# board2.net
KiCad netlist of a schematic drawn in EAGLE
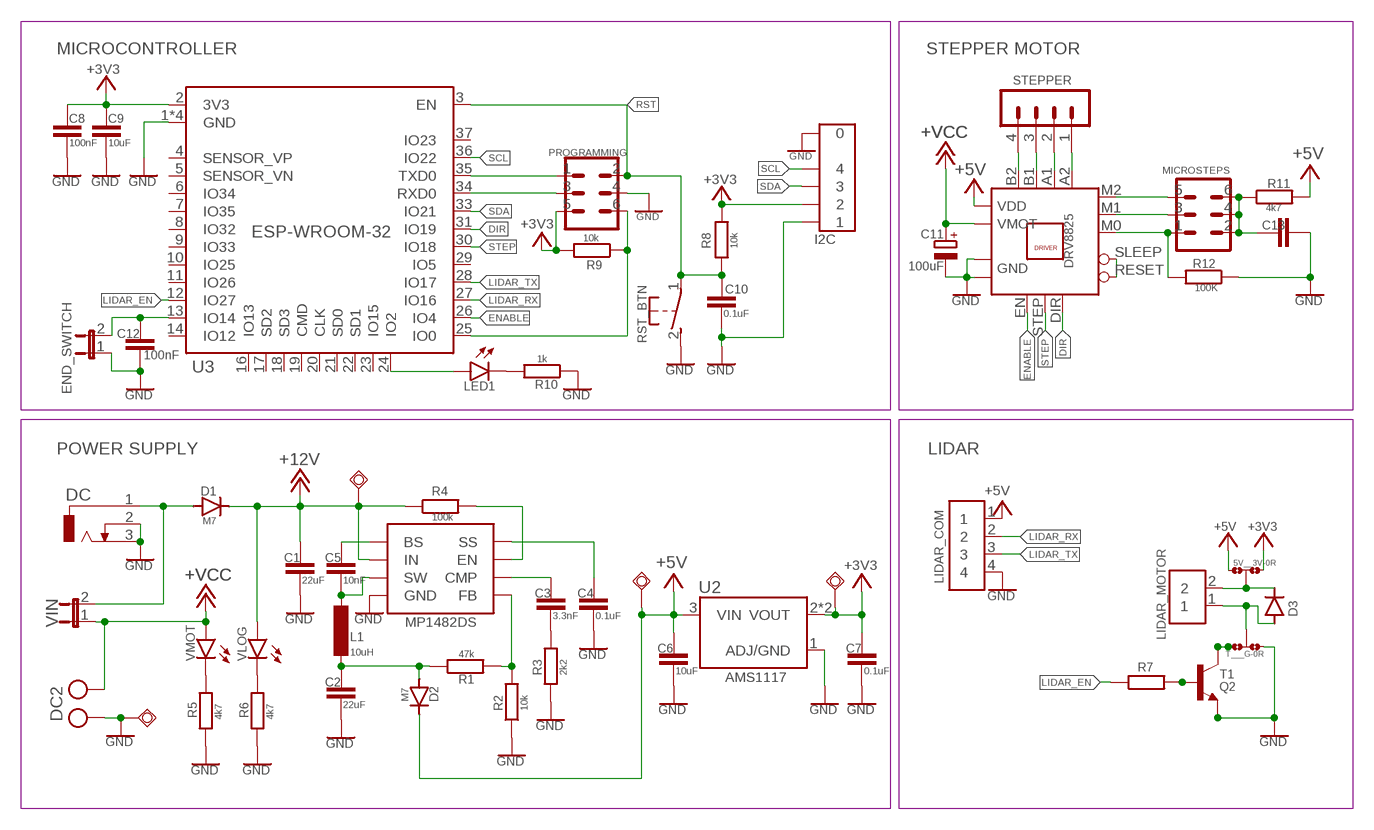
[diagram p0: schematic, sheet 1]

(export (version "E")
  (design (tool "Eeschema 10.0.6"))
  (components
    (comp (ref "3V3")
      (value "TPSQTP07R")
      (footprint "eagle-import:TP07R")
      (libsource (lib "eagle-import") (part "TPSQTP07R"))
    )
    (comp (ref "5V")
      (value "TPSQTP07R")
      (footprint "eagle-import:TP07R")
      (libsource (lib "eagle-import") (part "TPSQTP07R"))
    )
    (comp (ref "5V__3V")
      (value "0R-JUMPA")
      (footprint "eagle-import:A0R-JMP")
      (libsource (lib "eagle-import") (part "0R-JUMPA"))
    )
    (comp (ref "12V")
      (value "TPSQTP07R")
      (footprint "eagle-import:TP07R")
      (libsource (lib "eagle-import") (part "TPSQTP07R"))
    )
    (comp (ref "C1")
      (value "22uF")
      (footprint "eagle-import:C1210K")
      (libsource (lib "eagle-import") (part "C-EUC1210K"))
    )
    (comp (ref "C2")
      (value "22uF")
      (footprint "eagle-import:C1210K")
      (libsource (lib "eagle-import") (part "C-EUC1210K"))
    )
    (comp (ref "C3")
      (value "3.3nF")
      (footprint "eagle-import:C0805K")
      (libsource (lib "eagle-import") (part "C-EUC0805K"))
    )
    (comp (ref "C4")
      (value "0.1uF")
      (footprint "eagle-import:C0805K")
      (libsource (lib "eagle-import") (part "C-EUC0805K"))
    )
    (comp (ref "C5")
      (value "10nF")
      (footprint "eagle-import:C0805K")
      (libsource (lib "eagle-import") (part "C-EUC0805K"))
    )
    (comp (ref "C6")
      (value "10uF")
      (footprint "eagle-import:C1210K")
      (libsource (lib "eagle-import") (part "C-EUC1210K"))
    )
    (comp (ref "C7")
      (value "0.1uF")
      (footprint "eagle-import:C1210K")
      (libsource (lib "eagle-import") (part "C-EUC1210K"))
    )
    (comp (ref "C8")
      (value "100nF")
      (footprint "eagle-import:C0805K")
      (libsource (lib "eagle-import") (part "C-EUC0805K"))
    )
    (comp (ref "C9")
      (value "10uF")
      (footprint "eagle-import:C1210K")
      (libsource (lib "eagle-import") (part "C-EUC1210K"))
    )
    (comp (ref "C10")
      (value "0.1uF")
      (footprint "eagle-import:C0805K")
      (libsource (lib "eagle-import") (part "C-EUC0805K"))
    )
    (comp (ref "C11")
      (value "100uF")
      (footprint "eagle-import:E3,5-8")
      (libsource (lib "eagle-import") (part "CPOL-EUE3.5-8"))
    )
    (comp (ref "C12")
      (value "100nF")
      (footprint "eagle-import:C0805K")
      (libsource (lib "eagle-import") (part "C-EUC0805K"))
    )
    (comp (ref "C13")
      (value "C-EUC0805K")
      (footprint "eagle-import:C0805K")
      (libsource (lib "eagle-import") (part "C-EUC0805K"))
    )
    (comp (ref "D1")
      (value "M7")
      (footprint "eagle-import:DO-214AC")
      (libsource (lib "eagle-import") (part "DIODE-DO-214AC"))
    )
    (comp (ref "D2")
      (value "M7")
      (footprint "eagle-import:DO-214AC")
      (libsource (lib "eagle-import") (part "DIODE-DO-214AC"))
    )
    (comp (ref "D3")
      (value "M7")
      (footprint "eagle-import:DO-214AC")
      (libsource (lib "eagle-import") (part "DIODE-DO-214AC"))
    )
    (comp (ref "DC")
      (value "DCJ0202")
      (footprint "eagle-import:DCJ0202")
      (libsource (lib "eagle-import") (part "DCJ0202"))
    )
    (comp (ref "DC2")
      (value "DC2")
      (footprint "eagle-import:AK500_2-H")
      (libsource (lib "eagle-import") (part "AK500/2-H"))
    )
    (comp (ref "DRIVER")
      (value "DRV8825_PCB")
      (footprint "eagle-import:DRV8825_PCB")
      (libsource (lib "eagle-import") (part "DRV8825_PCB"))
    )
    (comp (ref "DRV8825")
      (value "DRV8825_H")
      (footprint "eagle-import:DRV8825_H")
      (libsource (lib "eagle-import") (part "DRV8825_H"))
    )
    (comp (ref "END_SWITCH")
      (value "END_SWITCH")
      (footprint "eagle-import:JP1")
      (libsource (lib "eagle-import") (part "JP1E"))
    )
    (comp (ref "GND")
      (value "TPSQTP07R")
      (footprint "eagle-import:TP07R")
      (libsource (lib "eagle-import") (part "TPSQTP07R"))
    )
    (comp (ref "I2C")
      (value "SM04B-SRSS-TB(LF)(SN)")
      (footprint "eagle-import:JST_SM04B-SRSS-TB(LF)(SN)")
      (fields (field (name "MF") "JST Sales"))
      (libsource (lib "eagle-import") (part "SM04B-SRSS-TB(LF)(SN)"))
    )
    (comp (ref "L1")
      (value "10uH")
      (footprint "eagle-import:L5650M")
      (libsource (lib "eagle-import") (part "L-EUL5650M"))
    )
    (comp (ref "LED1")
      (value "0")
      (footprint "eagle-import:CHIP-LED0805")
      (libsource (lib "eagle-import") (part "LEDCHIP-LED0805"))
    )
    (comp (ref "LIDAR_COM")
      (value "4PIN")
      (footprint "eagle-import:B4B-PH-K-S")
      (libsource (lib "eagle-import") (part "4PIN"))
    )
    (comp (ref "LIDAR_MOTOR")
      (value "2PIN")
      (footprint "eagle-import:B2B-PH-K-S")
      (libsource (lib "eagle-import") (part "2PIN"))
    )
    (comp (ref "MICROSTEPS")
      (value "MicroSteps")
      (footprint "eagle-import:MA03-2")
      (libsource (lib "eagle-import") (part "MA03-2"))
    )
    (comp (ref "PROGRAMMING")
      (value "Programming")
      (footprint "eagle-import:MA03-2")
      (libsource (lib "eagle-import") (part "MA03-2"))
    )
    (comp (ref "Q2")
      (value "BC846ALT1SMD")
      (footprint "eagle-import:SOT23")
      (libsource (lib "eagle-import") (part "BC846SMDALT1"))
    )
    (comp (ref "R1")
      (value "47k")
      (footprint "eagle-import:R0805W")
      (libsource (lib "eagle-import") (part "R-EU_R0805W"))
    )
    (comp (ref "R2")
      (value "10k")
      (footprint "eagle-import:R0805W")
      (libsource (lib "eagle-import") (part "R-EU_R0805W"))
    )
    (comp (ref "R3")
      (value "2k2")
      (footprint "eagle-import:R0805W")
      (libsource (lib "eagle-import") (part "R-EU_R0805W"))
    )
    (comp (ref "R4")
      (value "100k")
      (footprint "eagle-import:R0805W")
      (libsource (lib "eagle-import") (part "R-EU_R0805W"))
    )
    (comp (ref "R5")
      (value "4k7")
      (footprint "eagle-import:R0805W")
      (libsource (lib "eagle-import") (part "R-EU_R0805W"))
    )
    (comp (ref "R6")
      (value "4k7")
      (footprint "eagle-import:R0805W")
      (libsource (lib "eagle-import") (part "R-EU_R0805W"))
    )
    (comp (ref "R7")
      (value "R")
      (footprint "eagle-import:R0805W")
      (libsource (lib "eagle-import") (part "R-EU_R0805W"))
    )
    (comp (ref "R8")
      (value "10k")
      (footprint "eagle-import:R0805W")
      (libsource (lib "eagle-import") (part "R-EU_R0805W"))
    )
    (comp (ref "R9")
      (value "10k")
      (footprint "eagle-import:R0805W")
      (libsource (lib "eagle-import") (part "R-EU_R0805W"))
    )
    (comp (ref "R10")
      (value "1k")
      (footprint "eagle-import:R0805W")
      (libsource (lib "eagle-import") (part "R-EU_R0805W"))
    )
    (comp (ref "R11")
      (value "4k7")
      (footprint "eagle-import:R0805W")
      (libsource (lib "eagle-import") (part "R-EU_R0805W"))
    )
    (comp (ref "R12")
      (value "100K")
      (footprint "eagle-import:R0805W")
      (libsource (lib "eagle-import") (part "R-EU_R0805W"))
    )
    (comp (ref "RST_BTN")
      (value "DTSM-3")
      (footprint "eagle-import:DTSM-3")
      (libsource (lib "eagle-import") (part "DTSM-3"))
    )
    (comp (ref "STEPPER")
      (value "Stepper")
      (footprint "eagle-import:MA04-1")
      (libsource (lib "eagle-import") (part "MA04-1"))
    )
    (comp (ref "T1")
      (value "BD139_BCXXX")
      (footprint "eagle-import:TO126+TO92")
      (libsource (lib "eagle-import") (part "BDBC"))
    )
    (comp (ref "T___G")
      (value "0R-JUMPB")
      (footprint "eagle-import:B0R-JMP")
      (libsource (lib "eagle-import") (part "0R-JUMPB"))
    )
    (comp (ref "U1")
      (value "MP1482DS")
      (footprint "eagle-import:SOIC127P600X175-8N")
      (fields (field (name "MP1482DS") "MP1482DS"))
      (libsource (lib "eagle-import") (part "MP1482DS"))
    )
    (comp (ref "U2")
      (value "AMS1117")
      (footprint "eagle-import:SOT229P700X180-4N")
      (fields (field (name "MF") "Advanced Monolithic Systems"))
      (libsource (lib "eagle-import") (part "AMS1117"))
    )
    (comp (ref "U3")
      (value "ESP-WROOM-32")
      (footprint "eagle-import:ESP-WROOM-32")
      (libsource (lib "eagle-import") (part "ESP-WROOM-32"))
    )
    (comp (ref "VIN")
      (value "JUMPER")
      (footprint "eagle-import:JP1")
      (libsource (lib "eagle-import") (part "JP1E"))
    )
    (comp (ref "VLOG")
      (value "00")
      (footprint "eagle-import:CHIP-LED0805")
      (libsource (lib "eagle-import") (part "LEDCHIP-LED0805"))
    )
    (comp (ref "VMOT")
      (value "00")
      (footprint "eagle-import:CHIP-LED0805")
      (libsource (lib "eagle-import") (part "LEDCHIP-LED0805"))
    )
  )
  (nets
    (net (code "1") (name "+3V3") (class "Default")
      (node (ref "3V3") (pin "TP") (pinfunction "TP_TP") (pintype "input"))
      (node (ref "5V__3V") (pin "1") (pinfunction "1_1") (pintype "passive"))
      (node (ref "5V__3V") (pin "2") (pinfunction "2_2") (pintype "passive"))
      (node (ref "C7") (pin "1") (pinfunction "1_1") (pintype "passive"))
      (node (ref "C8") (pin "1") (pinfunction "1_1") (pintype "passive"))
      (node (ref "C9") (pin "1") (pinfunction "1_1") (pintype "passive"))
      (node (ref "D3") (pin "C") (pinfunction "C_C") (pintype "passive"))
      (node (ref "I2C") (pin "2") (pinfunction "2_2") (pintype "passive"))
      (node (ref "LIDAR_MOTOR") (pin "2") (pinfunction "2_2") (pintype "bidirectional"))
      (node (ref "PROGRAMMING") (pin "5") (pinfunction "5_5") (pintype "passive"))
      (node (ref "R8") (pin "1") (pinfunction "1_1") (pintype "passive"))
      (node (ref "R9") (pin "2") (pinfunction "2_2") (pintype "passive"))
      (node (ref "U2") (pin "2") (pinfunction "VOUT_2") (pintype "output"))
      (node (ref "U2") (pin "4") (pinfunction "VOUT_4") (pintype "output"))
      (node (ref "U3") (pin "2") (pinfunction "3V3_2") (pintype "power_in"))
    )
    (net (code "2") (name "+5V") (class "Default")
      (node (ref "5V") (pin "TP") (pinfunction "TP_TP") (pintype "input"))
      (node (ref "5V__3V") (pin "3") (pinfunction "3_3") (pintype "passive"))
      (node (ref "C6") (pin "2") (pinfunction "2_2") (pintype "passive"))
      (node (ref "D2") (pin "C") (pinfunction "C_C") (pintype "passive"))
      (node (ref "DRV8825") (pin "FAULT") (pinfunction "VDD_FAULT") (pintype "power_in"))
      (node (ref "LIDAR_COM") (pin "1") (pinfunction "1_1") (pintype "bidirectional"))
      (node (ref "R11") (pin "2") (pinfunction "2_2") (pintype "passive"))
      (node (ref "U2") (pin "3") (pinfunction "VIN_3") (pintype "input"))
    )
    (net (code "3") (name "+12V") (class "Default")
      (node (ref "12V") (pin "TP") (pinfunction "TP_TP") (pintype "input"))
      (node (ref "C1") (pin "2") (pinfunction "2_2") (pintype "passive"))
      (node (ref "D1") (pin "C") (pinfunction "C_C") (pintype "passive"))
      (node (ref "R4") (pin "1") (pinfunction "1_1") (pintype "passive"))
      (node (ref "U1") (pin "2") (pinfunction "IN_2") (pintype "power_in"))
      (node (ref "VLOG") (pin "A") (pinfunction "A_A") (pintype "passive"))
    )
    (net (code "4") (name "+VCC") (class "Default")
      (node (ref "C11") (pin "+") (pinfunction "+_+") (pintype "passive"))
      (node (ref "DC2") (pin "2") (pinfunction "KL_2") (pintype "passive"))
      (node (ref "DRV8825") (pin "VMOT") (pinfunction "VMOT_VMOT") (pintype "power_in"))
      (node (ref "DRV8825") (pin "VMOT1") (pinfunction "VMOT_VMOT1") (pintype "power_in"))
      (node (ref "VIN") (pin "1") (pinfunction "1_1") (pintype "passive"))
      (node (ref "VMOT") (pin "A") (pinfunction "A_A") (pintype "passive"))
    )
    (net (code "5") (name "DIR") (class "Default")
      (node (ref "DRV8825") (pin "DIR") (pinfunction "DIR_DIR") (pintype "input"))
      (node (ref "U3") (pin "31") (pinfunction "IO19_31") (pintype "bidirectional"))
    )
    (net (code "6") (name "ENABLE") (class "Default")
      (node (ref "DRV8825") (pin "EN") (pinfunction "EN_EN") (pintype "input"))
      (node (ref "U3") (pin "26") (pinfunction "IO4_26") (pintype "bidirectional"))
    )
    (net (code "7") (name "GND") (class "Default")
      (node (ref "C1") (pin "1") (pinfunction "1_1") (pintype "passive"))
      (node (ref "C10") (pin "2") (pinfunction "2_2") (pintype "passive"))
      (node (ref "C11") (pin "-") (pinfunction "-_-") (pintype "passive"))
      (node (ref "C12") (pin "1") (pinfunction "1_1") (pintype "passive"))
      (node (ref "C13") (pin "2") (pinfunction "2_2") (pintype "passive"))
      (node (ref "C2") (pin "2") (pinfunction "2_2") (pintype "passive"))
      (node (ref "C4") (pin "1") (pinfunction "1_1") (pintype "passive"))
      (node (ref "C6") (pin "1") (pinfunction "1_1") (pintype "passive"))
      (node (ref "C7") (pin "2") (pinfunction "2_2") (pintype "passive"))
      (node (ref "C8") (pin "2") (pinfunction "2_2") (pintype "passive"))
      (node (ref "C9") (pin "2") (pinfunction "2_2") (pintype "passive"))
      (node (ref "DC") (pin "2") (pinfunction "2_2") (pintype "passive"))
      (node (ref "DC") (pin "3") (pinfunction "3_3") (pintype "passive"))
      (node (ref "DC2") (pin "1") (pinfunction "KL_1") (pintype "passive"))
      (node (ref "DRV8825") (pin "GND") (pinfunction "GND_GND") (pintype "power_in"))
      (node (ref "DRV8825") (pin "GND1") (pinfunction "GMOT_GND1") (pintype "power_in"))
      (node (ref "END_SWITCH") (pin "1") (pinfunction "1_1") (pintype "passive"))
      (node (ref "GND") (pin "TP") (pinfunction "TP_TP") (pintype "input"))
      (node (ref "I2C") (pin "1") (pinfunction "1_1") (pintype "passive"))
      (node (ref "I2C") (pin "S1") (pinfunction "0_S1") (pintype "passive"))
      (node (ref "I2C") (pin "S2") (pinfunction "0_S2") (pintype "passive"))
      (node (ref "LIDAR_COM") (pin "4") (pinfunction "4_4") (pintype "bidirectional"))
      (node (ref "PROGRAMMING") (pin "4") (pinfunction "4_4") (pintype "passive"))
      (node (ref "Q2") (pin "2") (pinfunction "E_2") (pintype "passive"))
      (node (ref "R10") (pin "1") (pinfunction "1_1") (pintype "passive"))
      (node (ref "R12") (pin "1") (pinfunction "1_1") (pintype "passive"))
      (node (ref "R2") (pin "1") (pinfunction "1_1") (pintype "passive"))
      (node (ref "R3") (pin "1") (pinfunction "1_1") (pintype "passive"))
      (node (ref "R5") (pin "1") (pinfunction "1_1") (pintype "passive"))
      (node (ref "R6") (pin "1") (pinfunction "1_1") (pintype "passive"))
      (node (ref "RST_BTN") (pin "2") (pinfunction "2_2") (pintype "passive"))
      (node (ref "T1") (pin "E") (pinfunction "E_E") (pintype "passive"))
      (node (ref "T1") (pin "E1") (pinfunction "E_E1") (pintype "passive"))
      (node (ref "T___G") (pin "3") (pinfunction "3_3") (pintype "passive"))
      (node (ref "U1") (pin "4") (pinfunction "GND_4") (pintype "power_in"))
      (node (ref "U2") (pin "1") (pinfunction "ADJ/GND_1") (pintype "power_in"))
      (node (ref "U3") (pin "1") (pinfunction "GND_1") (pintype "power_in"))
      (node (ref "U3") (pin "15") (pinfunction "GND_15") (pintype "power_in"))
      (node (ref "U3") (pin "38") (pinfunction "GND_38") (pintype "power_in"))
      (node (ref "U3") (pin "GND") (pinfunction "GND_GND") (pintype "power_in"))
    )
    (net (code "8") (name "LIDAR_EN") (class "Default")
      (node (ref "R7") (pin "1") (pinfunction "1_1") (pintype "passive"))
      (node (ref "U3") (pin "12") (pinfunction "IO27_12") (pintype "bidirectional"))
    )
    (net (code "9") (name "LIDAR_RX") (class "Default")
      (node (ref "LIDAR_COM") (pin "2") (pinfunction "2_2") (pintype "bidirectional"))
      (node (ref "U3") (pin "27") (pinfunction "IO16_27") (pintype "bidirectional"))
    )
    (net (code "10") (name "LIDAR_TX") (class "Default")
      (node (ref "LIDAR_COM") (pin "3") (pinfunction "3_3") (pintype "bidirectional"))
      (node (ref "U3") (pin "28") (pinfunction "IO17_28") (pintype "bidirectional"))
    )
    (net (code "11") (name "Net-(C2-Pad1)") (class "Default")
      (node (ref "C2") (pin "1") (pinfunction "1_1") (pintype "passive"))
      (node (ref "D2") (pin "A") (pinfunction "A_A") (pintype "passive"))
      (node (ref "L1") (pin "1") (pinfunction "1_1") (pintype "passive"))
      (node (ref "R1") (pin "1") (pinfunction "1_1") (pintype "passive"))
    )
    (net (code "12") (name "Net-(C3-Pad1)") (class "Default")
      (node (ref "C3") (pin "1") (pinfunction "1_1") (pintype "passive"))
      (node (ref "R3") (pin "2") (pinfunction "2_2") (pintype "passive"))
    )
    (net (code "13") (name "Net-(C13-Pad1)") (class "Default")
      (node (ref "C13") (pin "1") (pinfunction "1_1") (pintype "passive"))
      (node (ref "MICROSTEPS") (pin "2") (pinfunction "2_2") (pintype "passive"))
      (node (ref "MICROSTEPS") (pin "4") (pinfunction "4_4") (pintype "passive"))
      (node (ref "MICROSTEPS") (pin "6") (pinfunction "6_6") (pintype "passive"))
      (node (ref "R11") (pin "1") (pinfunction "1_1") (pintype "passive"))
    )
    (net (code "14") (name "Net-(D1-PadA)") (class "Default")
      (node (ref "D1") (pin "A") (pinfunction "A_A") (pintype "passive"))
      (node (ref "DC") (pin "1") (pinfunction "1_1") (pintype "passive"))
      (node (ref "VIN") (pin "2") (pinfunction "2_2") (pintype "passive"))
    )
    (net (code "15") (name "Net-(D3-PadA)") (class "Default")
      (node (ref "D3") (pin "A") (pinfunction "A_A") (pintype "passive"))
      (node (ref "LIDAR_MOTOR") (pin "1") (pinfunction "1_1") (pintype "bidirectional"))
      (node (ref "T___G") (pin "2") (pinfunction "2_2") (pintype "passive"))
    )
    (net (code "16") (name "Net-(DRV8825-PadA1)") (class "Default")
      (node (ref "DRV8825") (pin "A1") (pinfunction "A1_A1") (pintype "bidirectional"))
      (node (ref "STEPPER") (pin "2") (pinfunction "2_2") (pintype "passive"))
    )
    (net (code "17") (name "Net-(DRV8825-PadA2)") (class "Default")
      (node (ref "DRV8825") (pin "A2") (pinfunction "A2_A2") (pintype "bidirectional"))
      (node (ref "STEPPER") (pin "1") (pinfunction "1_1") (pintype "passive"))
    )
    (net (code "18") (name "Net-(DRV8825-PadB1)") (class "Default")
      (node (ref "DRV8825") (pin "B1") (pinfunction "B1_B1") (pintype "bidirectional"))
      (node (ref "STEPPER") (pin "3") (pinfunction "3_3") (pintype "passive"))
    )
    (net (code "19") (name "Net-(DRV8825-PadB2)") (class "Default")
      (node (ref "DRV8825") (pin "B2") (pinfunction "B2_B2") (pintype "bidirectional"))
      (node (ref "STEPPER") (pin "4") (pinfunction "4_4") (pintype "passive"))
    )
    (net (code "20") (name "Net-(DRV8825-PadM0)") (class "Default")
      (node (ref "DRV8825") (pin "M0") (pinfunction "M0_M0") (pintype "input"))
      (node (ref "MICROSTEPS") (pin "1") (pinfunction "1_1") (pintype "passive"))
      (node (ref "R12") (pin "2") (pinfunction "2_2") (pintype "passive"))
    )
    (net (code "21") (name "Net-(DRV8825-PadM1)") (class "Default")
      (node (ref "DRV8825") (pin "M1") (pinfunction "M1_M1") (pintype "input"))
      (node (ref "MICROSTEPS") (pin "3") (pinfunction "3_3") (pintype "passive"))
    )
    (net (code "22") (name "Net-(DRV8825-PadM2)") (class "Default")
      (node (ref "DRV8825") (pin "M2") (pinfunction "M2_M2") (pintype "input"))
      (node (ref "MICROSTEPS") (pin "5") (pinfunction "5_5") (pintype "passive"))
    )
    (net (code "23") (name "Net-(DRV8825-PadRESET)") (class "Default")
      (node (ref "DRV8825") (pin "RESET") (pinfunction "RESET_RESET") (pintype "bidirectional"))
      (node (ref "DRV8825") (pin "SLEEP") (pinfunction "SLEEP_SLEEP") (pintype "bidirectional"))
    )
    (net (code "24") (name "Net-(LED1-PadC)") (class "Default")
      (node (ref "LED1") (pin "C") (pinfunction "C_C") (pintype "passive"))
      (node (ref "R10") (pin "2") (pinfunction "2_2") (pintype "passive"))
    )
    (net (code "25") (name "Net-(Q2-B)") (class "Default")
      (node (ref "Q2") (pin "1") (pinfunction "B_1") (pintype "passive"))
      (node (ref "R7") (pin "2") (pinfunction "2_2") (pintype "passive"))
      (node (ref "T1") (pin "B") (pinfunction "B_B") (pintype "passive"))
    )
    (net (code "26") (name "Net-(Q2-C)") (class "Default")
      (node (ref "Q2") (pin "3") (pinfunction "C_3") (pintype "passive"))
      (node (ref "T1") (pin "C") (pinfunction "C_C") (pintype "passive"))
      (node (ref "T___G") (pin "1") (pinfunction "1_1") (pintype "passive"))
    )
    (net (code "27") (name "Net-(R5-Pad2)") (class "Default")
      (node (ref "R5") (pin "2") (pinfunction "2_2") (pintype "passive"))
      (node (ref "VMOT") (pin "C") (pinfunction "C_C") (pintype "passive"))
    )
    (net (code "28") (name "Net-(R6-Pad2)") (class "Default")
      (node (ref "R6") (pin "2") (pinfunction "2_2") (pintype "passive"))
      (node (ref "VLOG") (pin "C") (pinfunction "C_C") (pintype "passive"))
    )
    (net (code "29") (name "Net-(U1-BS)") (class "Default")
      (node (ref "C5") (pin "2") (pinfunction "2_2") (pintype "passive"))
      (node (ref "U1") (pin "1") (pinfunction "BS_1") (pintype "bidirectional"))
    )
    (net (code "30") (name "Net-(U1-CMP)") (class "Default")
      (node (ref "C3") (pin "2") (pinfunction "2_2") (pintype "passive"))
      (node (ref "U1") (pin "6") (pinfunction "CMP_6") (pintype "bidirectional"))
    )
    (net (code "31") (name "Net-(U1-EN)") (class "Default")
      (node (ref "R4") (pin "2") (pinfunction "2_2") (pintype "passive"))
      (node (ref "U1") (pin "7") (pinfunction "EN_7") (pintype "bidirectional"))
    )
    (net (code "32") (name "Net-(U1-FB)") (class "Default")
      (node (ref "R1") (pin "2") (pinfunction "2_2") (pintype "passive"))
      (node (ref "R2") (pin "2") (pinfunction "2_2") (pintype "passive"))
      (node (ref "U1") (pin "5") (pinfunction "FB_5") (pintype "bidirectional"))
    )
    (net (code "33") (name "Net-(U1-SS)") (class "Default")
      (node (ref "C4") (pin "2") (pinfunction "2_2") (pintype "passive"))
      (node (ref "U1") (pin "8") (pinfunction "SS_8") (pintype "bidirectional"))
    )
    (net (code "34") (name "Net-(U1-SW)") (class "Default")
      (node (ref "C5") (pin "1") (pinfunction "1_1") (pintype "passive"))
      (node (ref "L1") (pin "2") (pinfunction "2_2") (pintype "passive"))
      (node (ref "U1") (pin "3") (pinfunction "SW_3") (pintype "bidirectional"))
    )
    (net (code "35") (name "Net-(U3-IO0)") (class "Default")
      (node (ref "PROGRAMMING") (pin "6") (pinfunction "6_6") (pintype "passive"))
      (node (ref "R9") (pin "1") (pinfunction "1_1") (pintype "passive"))
      (node (ref "U3") (pin "25") (pinfunction "IO0_25") (pintype "bidirectional"))
    )
    (net (code "36") (name "Net-(U3-IO2)") (class "Default")
      (node (ref "LED1") (pin "A") (pinfunction "A_A") (pintype "passive"))
      (node (ref "U3") (pin "24") (pinfunction "IO2_24") (pintype "bidirectional"))
    )
    (net (code "37") (name "Net-(U3-IO14)") (class "Default")
      (node (ref "C12") (pin "2") (pinfunction "2_2") (pintype "passive"))
      (node (ref "END_SWITCH") (pin "2") (pinfunction "2_2") (pintype "passive"))
      (node (ref "U3") (pin "13") (pinfunction "IO14_13") (pintype "bidirectional"))
    )
    (net (code "38") (name "Net-(U3-RXD0)") (class "Default")
      (node (ref "PROGRAMMING") (pin "3") (pinfunction "3_3") (pintype "passive"))
      (node (ref "U3") (pin "34") (pinfunction "RXD0_34") (pintype "bidirectional"))
    )
    (net (code "39") (name "Net-(U3-TXD0)") (class "Default")
      (node (ref "PROGRAMMING") (pin "1") (pinfunction "1_1") (pintype "passive"))
      (node (ref "U3") (pin "35") (pinfunction "TXD0_35") (pintype "bidirectional"))
    )
    (net (code "40") (name "RST") (class "Default")
      (node (ref "C10") (pin "1") (pinfunction "1_1") (pintype "passive"))
      (node (ref "PROGRAMMING") (pin "2") (pinfunction "2_2") (pintype "passive"))
      (node (ref "R8") (pin "2") (pinfunction "2_2") (pintype "passive"))
      (node (ref "RST_BTN") (pin "1") (pinfunction "1_1") (pintype "passive"))
      (node (ref "U3") (pin "3") (pinfunction "EN_3") (pintype "input"))
    )
    (net (code "41") (name "SCL") (class "Default")
      (node (ref "I2C") (pin "4") (pinfunction "4_4") (pintype "passive"))
      (node (ref "U3") (pin "36") (pinfunction "IO22_36") (pintype "bidirectional"))
    )
    (net (code "42") (name "SDA") (class "Default")
      (node (ref "I2C") (pin "3") (pinfunction "3_3") (pintype "passive"))
      (node (ref "U3") (pin "33") (pinfunction "IO21_33") (pintype "bidirectional"))
    )
    (net (code "43") (name "STEP") (class "Default")
      (node (ref "DRV8825") (pin "STEP") (pinfunction "STEP_STEP") (pintype "input"))
      (node (ref "U3") (pin "30") (pinfunction "IO18_30") (pintype "bidirectional"))
    )
    (net (code "44") (name "unconnected-(U3-CLK-Pad20)") (class "Default")
      (node (ref "U3") (pin "20") (pinfunction "CLK_20") (pintype "bidirectional"))
    )
    (net (code "45") (name "unconnected-(U3-CMD-Pad19)") (class "Default")
      (node (ref "U3") (pin "19") (pinfunction "CMD_19") (pintype "bidirectional"))
    )
    (net (code "46") (name "unconnected-(U3-IO5-Pad29)") (class "Default")
      (node (ref "U3") (pin "29") (pinfunction "IO5_29") (pintype "bidirectional"))
    )
    (net (code "47") (name "unconnected-(U3-IO12-Pad14)") (class "Default")
      (node (ref "U3") (pin "14") (pinfunction "IO12_14") (pintype "bidirectional"))
    )
    (net (code "48") (name "unconnected-(U3-IO13-Pad16)") (class "Default")
      (node (ref "U3") (pin "16") (pinfunction "IO13_16") (pintype "bidirectional"))
    )
    (net (code "49") (name "unconnected-(U3-IO15-Pad23)") (class "Default")
      (node (ref "U3") (pin "23") (pinfunction "IO15_23") (pintype "bidirectional"))
    )
    (net (code "50") (name "unconnected-(U3-IO23-Pad37)") (class "Default")
      (node (ref "U3") (pin "37") (pinfunction "IO23_37") (pintype "bidirectional"))
    )
    (net (code "51") (name "unconnected-(U3-IO25-Pad10)") (class "Default")
      (node (ref "U3") (pin "10") (pinfunction "IO25_10") (pintype "bidirectional"))
    )
    (net (code "52") (name "unconnected-(U3-IO26-Pad11)") (class "Default")
      (node (ref "U3") (pin "11") (pinfunction "IO26_11") (pintype "bidirectional"))
    )
    (net (code "53") (name "unconnected-(U3-IO32-Pad8)") (class "Default")
      (node (ref "U3") (pin "8") (pinfunction "IO32_8") (pintype "bidirectional"))
    )
    (net (code "54") (name "unconnected-(U3-IO33-Pad9)") (class "Default")
      (node (ref "U3") (pin "9") (pinfunction "IO33_9") (pintype "bidirectional"))
    )
    (net (code "55") (name "unconnected-(U3-IO34-Pad6)") (class "Default")
      (node (ref "U3") (pin "6") (pinfunction "IO34_6") (pintype "bidirectional"))
    )
    (net (code "56") (name "unconnected-(U3-IO35-Pad7)") (class "Default")
      (node (ref "U3") (pin "7") (pinfunction "IO35_7") (pintype "bidirectional"))
    )
    (net (code "57") (name "unconnected-(U3-SD0-Pad21)") (class "Default")
      (node (ref "U3") (pin "21") (pinfunction "SD0_21") (pintype "bidirectional"))
    )
    (net (code "58") (name "unconnected-(U3-SD1-Pad22)") (class "Default")
      (node (ref "U3") (pin "22") (pinfunction "SD1_22") (pintype "bidirectional"))
    )
    (net (code "59") (name "unconnected-(U3-SD2-Pad17)") (class "Default")
      (node (ref "U3") (pin "17") (pinfunction "SD2_17") (pintype "bidirectional"))
    )
    (net (code "60") (name "unconnected-(U3-SD3-Pad18)") (class "Default")
      (node (ref "U3") (pin "18") (pinfunction "SD3_18") (pintype "bidirectional"))
    )
    (net (code "61") (name "unconnected-(U3-SENSOR_VN-Pad5)") (class "Default")
      (node (ref "U3") (pin "5") (pinfunction "SENSOR_VN_5") (pintype "bidirectional"))
    )
    (net (code "62") (name "unconnected-(U3-SENSOR_VP-Pad4)") (class "Default")
      (node (ref "U3") (pin "4") (pinfunction "SENSOR_VP_4") (pintype "bidirectional"))
    )
  )
)
